# ProProject__2_2023-12-08.net
KiCad netlist of a schematic drawn in EasyEDA Pro
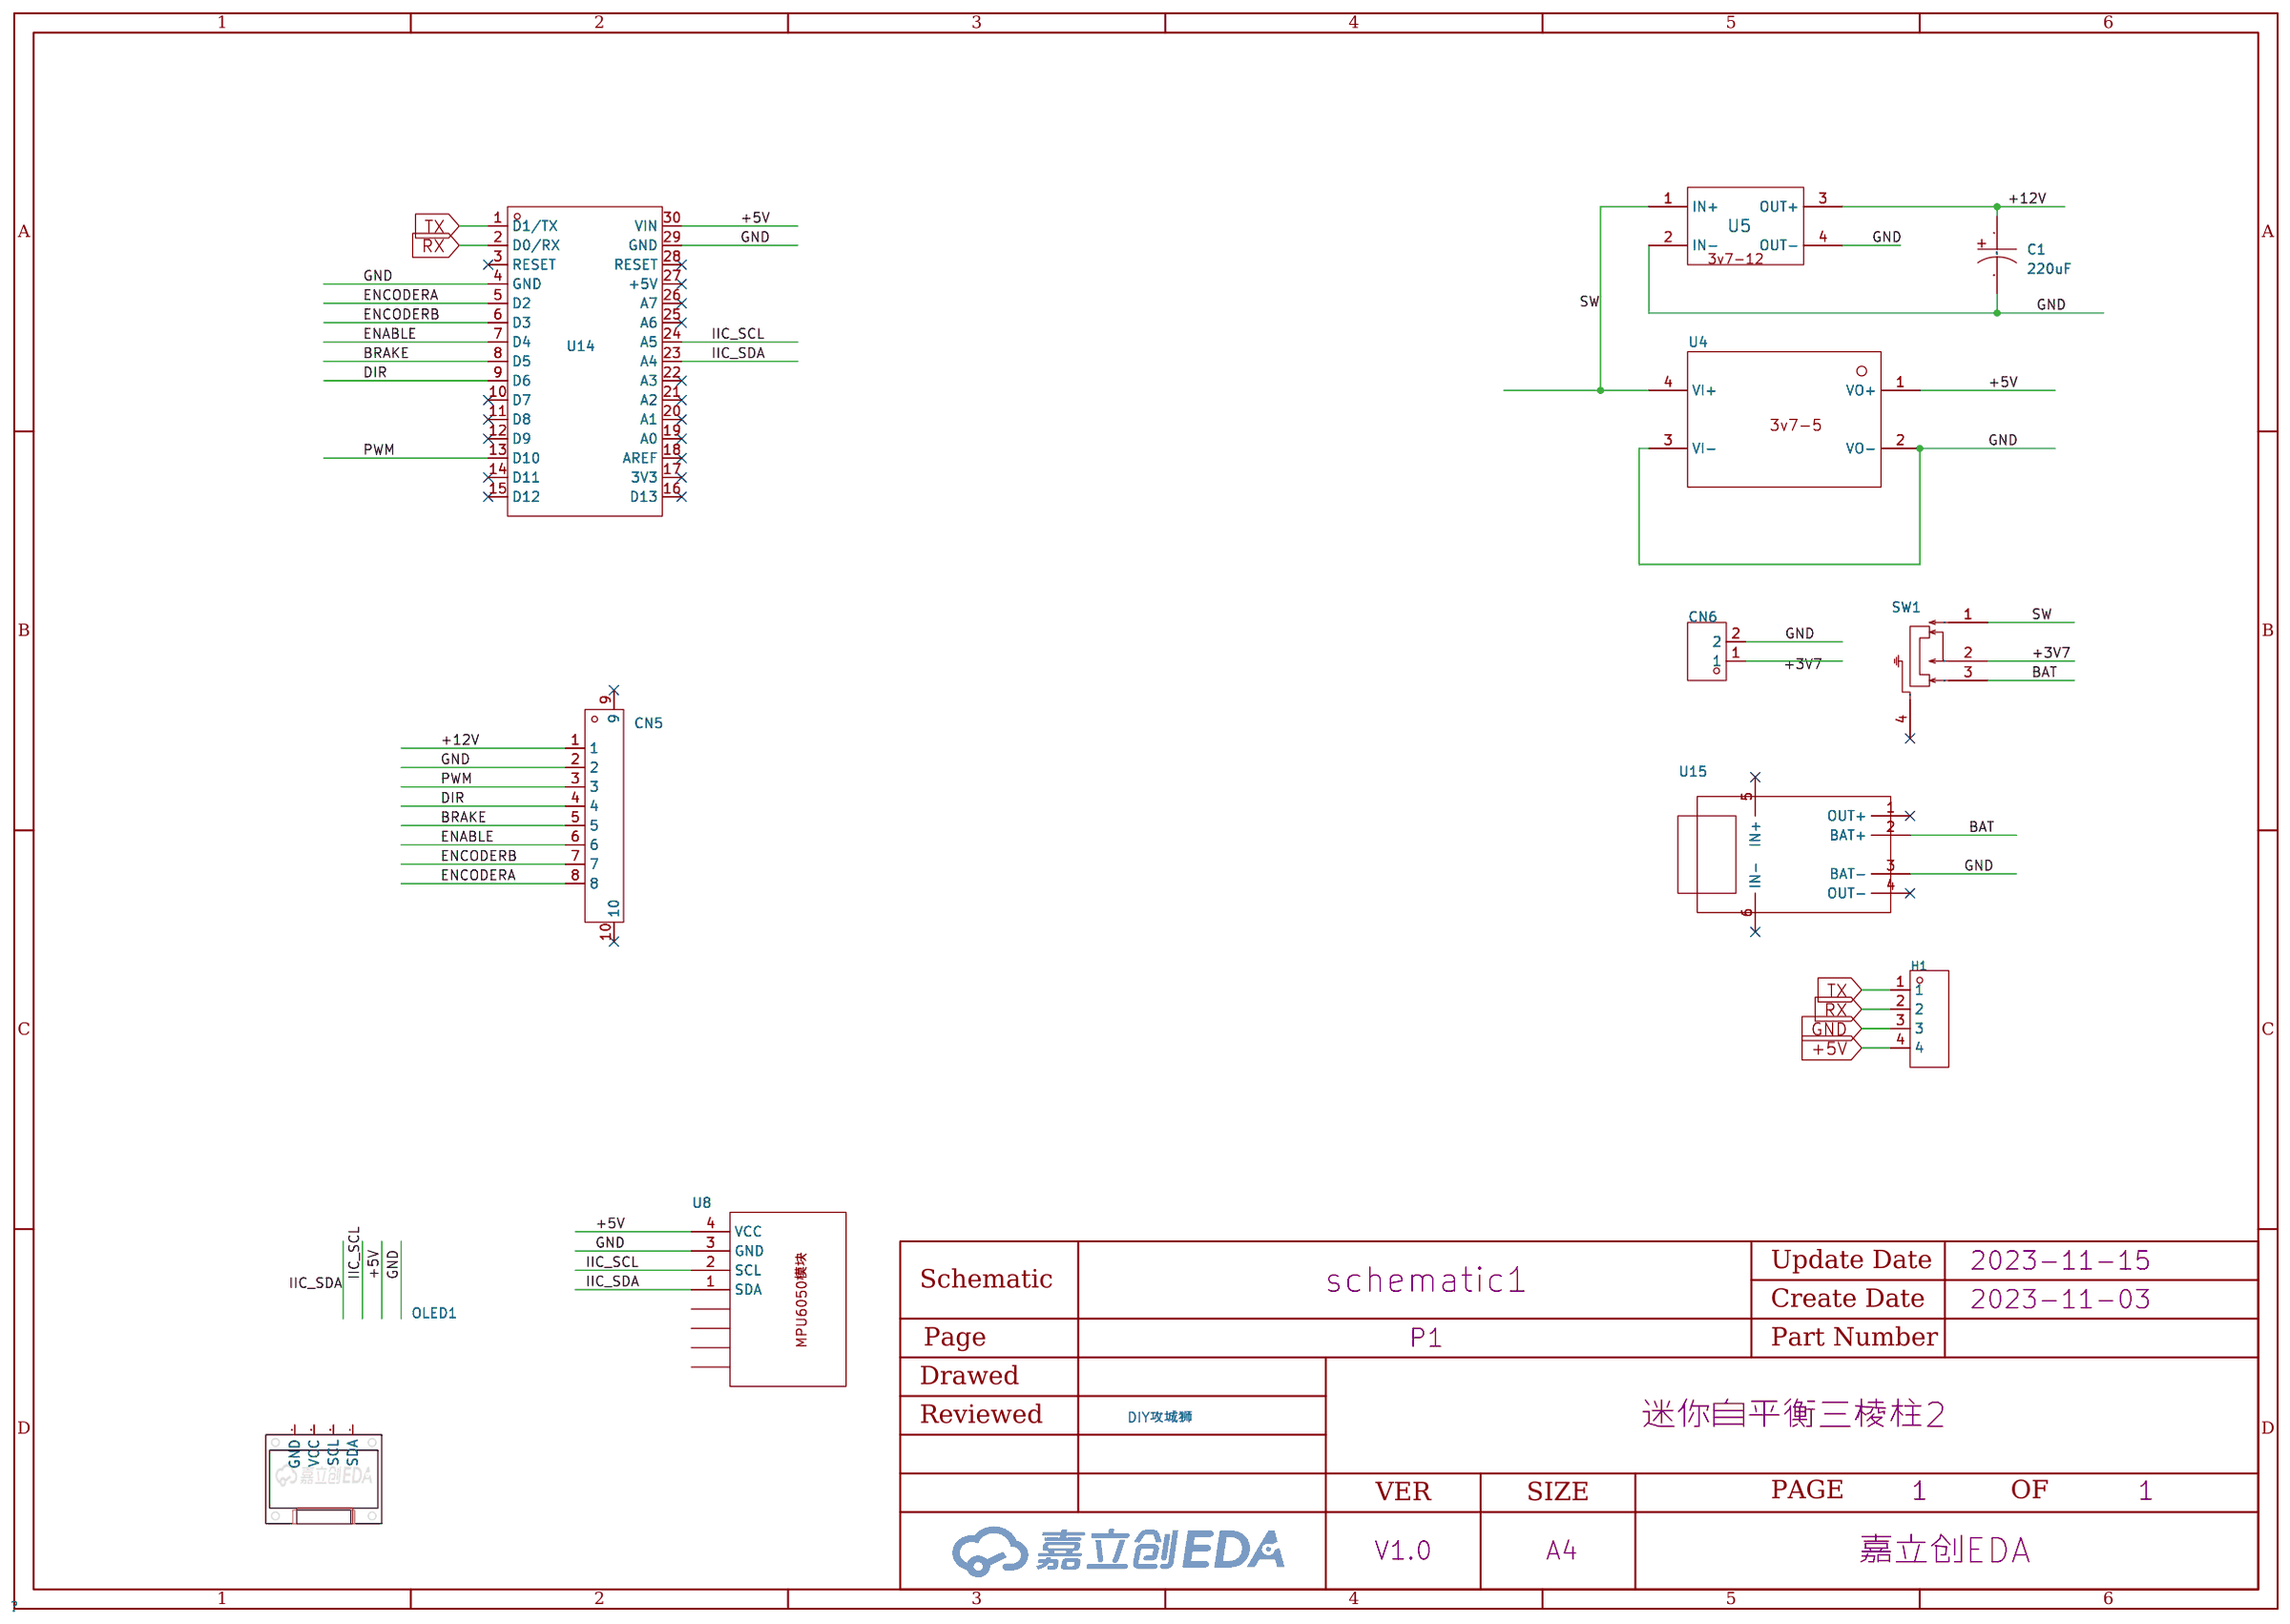
[diagram p0: schematic sheet]

(export (version "E")
  (design (tool "Eeschema 10.0.6"))
  (components
    (comp (ref "C1")
      (value "220uF")
      (footprint "easyedapro:CAP-SMD_BD8.0-L8.3-W8.3-FD")
      (fields (field (name "Manufacturer Part") "EEEFP1V221AP") (field (name "Manufacturer") "PANASONIC(松下)"))
      (libsource (lib "easyedapro") (part "EEEFP1V221AP"))
    )
    (comp (ref "CN5")
      (value "GH1.25-8PLTPZ")
      (footprint "easyedapro:CONN-SMD_GH1.25-8PLTPZ")
      (fields (field (name "Manufacturer") "BOOMELE(博穆精密)"))
      (libsource (lib "easyedapro") (part "GH1.25-8PLTPZ"))
    )
    (comp (ref "CN6")
      (value "B2B-XH-A(LF)(SN)")
      (footprint "easyedapro:CONN-TH_2P-P2.50-XH2.54-2P")
      (fields (field (name "Manufacturer") "JST"))
      (libsource (lib "easyedapro") (part "HX25037-2A_C9900012767"))
    )
    (comp (ref "H1")
      (value "~")
      (footprint "easyedapro:HDR-TH_4P-P2.54-V-M")
      (libsource (lib "easyedapro") (part "PZ254V-11-04P"))
    )
    (comp (ref "OLED1")
      (value "~")
      (footprint "easyedapro:0.96OLED_4P")
      (libsource (lib "easyedapro") (part "0.96OLED模块_4P"))
    )
    (comp (ref "SW1")
      (value "HX MSK12CO2-BBTM")
      (footprint "easyedapro:SW-SMD_MSK12C02-HB")
      (fields (field (name "Manufacturer") "hanxia(韩下)"))
      (libsource (lib "easyedapro") (part "HX MSK12CO2-BBTM"))
    )
    (comp (ref "U4")
      (value "DM13-05")
      (footprint "easyedapro:DM13-05")
      (libsource (lib "easyedapro") (part "DM13-05"))
    )
    (comp (ref "U5")
      (value "~")
      (footprint "easyedapro:DC3V7-DC12")
      (libsource (lib "easyedapro") (part "DC3V7-DC12"))
    )
    (comp (ref "U8")
      (value "~")
      (footprint "easyedapro:MPU-6050模块")
      (description "MPU-6050模块")
      (libsource (lib "easyedapro") (part "MPU-6050模块"))
    )
    (comp (ref "U14")
      (value "ARDUINO_NANO")
      (footprint "easyedapro:COMM-TH_ARDUINO_NANO")
      (libsource (lib "easyedapro") (part "ARDUINO_NANO"))
    )
    (comp (ref "U15")
      (value "~")
      (footprint "easyedapro:TP4057模块封装")
      (libsource (lib "easyedapro") (part "TP4057模块"))
    )
  )
  (nets
    (net (code "1") (name "+5V") (class "Default")
      (node (ref "H1") (pin "4") (pinfunction "4_4") (pintype "input"))
      (node (ref "U14") (pin "30") (pinfunction "VIN_30") (pintype "input"))
      (node (ref "U4") (pin "1") (pinfunction "VO+_1") (pintype "unspecified"))
      (node (ref "U8") (pin "4") (pinfunction "VCC_4") (pintype "input"))
    )
    (net (code "2") (name "/+3V7") (class "Default")
      (node (ref "CN6") (pin "1") (pinfunction "1_1") (pintype "input"))
      (node (ref "SW1") (pin "2") (pinfunction "2_2") (pintype "input"))
    )
    (net (code "3") (name "/+12V") (class "Default")
      (node (ref "C1") (pin "1") (pinfunction "1_1") (pintype "input"))
      (node (ref "CN5") (pin "1") (pinfunction "1_1") (pintype "input"))
      (node (ref "U5") (pin "3") (pinfunction "OUT+_3") (pintype "unspecified"))
    )
    (net (code "4") (name "/BAT") (class "Default")
      (node (ref "SW1") (pin "3") (pinfunction "3_3") (pintype "input"))
      (node (ref "U15") (pin "2") (pinfunction "BAT+_2") (pintype "input"))
    )
    (net (code "5") (name "/BRAKE") (class "Default")
      (node (ref "CN5") (pin "5") (pinfunction "5_5") (pintype "input"))
      (node (ref "U14") (pin "8") (pinfunction "D5_8") (pintype "input"))
    )
    (net (code "6") (name "/DIR") (class "Default")
      (node (ref "CN5") (pin "4") (pinfunction "4_4") (pintype "input"))
      (node (ref "U14") (pin "9") (pinfunction "D6_9") (pintype "input"))
    )
    (net (code "7") (name "/ENABLE") (class "Default")
      (node (ref "CN5") (pin "6") (pinfunction "6_6") (pintype "input"))
      (node (ref "U14") (pin "7") (pinfunction "D4_7") (pintype "input"))
    )
    (net (code "8") (name "/ENCODERA") (class "Default")
      (node (ref "CN5") (pin "8") (pinfunction "8_8") (pintype "input"))
      (node (ref "U14") (pin "5") (pinfunction "D2_5") (pintype "input"))
    )
    (net (code "9") (name "/ENCODERB") (class "Default")
      (node (ref "CN5") (pin "7") (pinfunction "7_7") (pintype "input"))
      (node (ref "U14") (pin "6") (pinfunction "D3_6") (pintype "input"))
    )
    (net (code "10") (name "/IIC_SCL") (class "Default")
      (node (ref "U14") (pin "24") (pinfunction "A5_24") (pintype "input"))
      (node (ref "U8") (pin "2") (pinfunction "SCL_2") (pintype "input"))
    )
    (net (code "11") (name "/IIC_SDA") (class "Default")
      (node (ref "U14") (pin "23") (pinfunction "A4_23") (pintype "input"))
      (node (ref "U8") (pin "1") (pinfunction "SDA_1") (pintype "input"))
    )
    (net (code "12") (name "/PWM") (class "Default")
      (node (ref "CN5") (pin "3") (pinfunction "3_3") (pintype "input"))
      (node (ref "U14") (pin "13") (pinfunction "D10_13") (pintype "input"))
    )
    (net (code "13") (name "/SW") (class "Default")
      (node (ref "SW1") (pin "1") (pinfunction "1_1") (pintype "input"))
      (node (ref "U4") (pin "4") (pinfunction "VI+_4") (pintype "unspecified"))
      (node (ref "U5") (pin "1") (pinfunction "IN+_1") (pintype "unspecified"))
    )
    (net (code "14") (name "GND") (class "Default")
      (node (ref "C1") (pin "2") (pinfunction "2_2") (pintype "input"))
      (node (ref "CN5") (pin "2") (pinfunction "2_2") (pintype "input"))
      (node (ref "CN6") (pin "2") (pinfunction "2_2") (pintype "input"))
      (node (ref "H1") (pin "3") (pinfunction "3_3") (pintype "input"))
      (node (ref "U14") (pin "29") (pinfunction "GND_29") (pintype "input"))
      (node (ref "U14") (pin "4") (pinfunction "GND_4") (pintype "input"))
      (node (ref "U15") (pin "3") (pinfunction "BAT-_3") (pintype "input"))
      (node (ref "U4") (pin "2") (pinfunction "VO-_2") (pintype "unspecified"))
      (node (ref "U4") (pin "3") (pinfunction "VI-_3") (pintype "unspecified"))
      (node (ref "U5") (pin "2") (pinfunction "IN-_2") (pintype "unspecified"))
      (node (ref "U5") (pin "4") (pinfunction "OUT-_4") (pintype "unspecified"))
      (node (ref "U8") (pin "3") (pinfunction "GND_3") (pintype "input"))
    )
    (net (code "15") (name "RX") (class "Default")
      (node (ref "H1") (pin "2") (pinfunction "2_2") (pintype "input"))
      (node (ref "U14") (pin "2") (pinfunction "D0/RX_2") (pintype "input"))
    )
    (net (code "16") (name "TX") (class "Default")
      (node (ref "H1") (pin "1") (pinfunction "1_1") (pintype "input"))
      (node (ref "U14") (pin "1") (pinfunction "D1/TX_1") (pintype "input"))
    )
    (net (code "17") (name "unconnected-(CN5-Pad9)") (class "Default")
      (node (ref "CN5") (pin "9") (pinfunction "9_9") (pintype "input+no_connect"))
    )
    (net (code "18") (name "unconnected-(CN5-Pad10)") (class "Default")
      (node (ref "CN5") (pin "10") (pinfunction "10_10") (pintype "input+no_connect"))
    )
    (net (code "19") (name "unconnected-(OLED1-GND-Pad1)") (class "Default")
      (node (ref "OLED1") (pin "1") (pinfunction "GND_1") (pintype "input"))
    )
    (net (code "20") (name "unconnected-(OLED1-SCL-Pad3)") (class "Default")
      (node (ref "OLED1") (pin "3") (pinfunction "SCL_3") (pintype "input"))
    )
    (net (code "21") (name "unconnected-(OLED1-SDA-Pad4)") (class "Default")
      (node (ref "OLED1") (pin "4") (pinfunction "SDA_4") (pintype "input"))
    )
    (net (code "22") (name "unconnected-(OLED1-VCC-Pad2)") (class "Default")
      (node (ref "OLED1") (pin "2") (pinfunction "VCC_2") (pintype "input"))
    )
    (net (code "23") (name "unconnected-(SW1-Pad4)") (class "Default")
      (node (ref "SW1") (pin "4") (pinfunction "4_4") (pintype "input+no_connect"))
    )
    (net (code "24") (name "unconnected-(U14-+5V-Pad27)") (class "Default")
      (node (ref "U14") (pin "27") (pinfunction "+5V_27") (pintype "input+no_connect"))
    )
    (net (code "25") (name "unconnected-(U14-3V3-Pad17)") (class "Default")
      (node (ref "U14") (pin "17") (pinfunction "3V3_17") (pintype "input+no_connect"))
    )
    (net (code "26") (name "unconnected-(U14-A0-Pad19)") (class "Default")
      (node (ref "U14") (pin "19") (pinfunction "A0_19") (pintype "input+no_connect"))
    )
    (net (code "27") (name "unconnected-(U14-A1-Pad20)") (class "Default")
      (node (ref "U14") (pin "20") (pinfunction "A1_20") (pintype "input+no_connect"))
    )
    (net (code "28") (name "unconnected-(U14-A2-Pad21)") (class "Default")
      (node (ref "U14") (pin "21") (pinfunction "A2_21") (pintype "input+no_connect"))
    )
    (net (code "29") (name "unconnected-(U14-A3-Pad22)") (class "Default")
      (node (ref "U14") (pin "22") (pinfunction "A3_22") (pintype "input+no_connect"))
    )
    (net (code "30") (name "unconnected-(U14-A6-Pad25)") (class "Default")
      (node (ref "U14") (pin "25") (pinfunction "A6_25") (pintype "input+no_connect"))
    )
    (net (code "31") (name "unconnected-(U14-A7-Pad26)") (class "Default")
      (node (ref "U14") (pin "26") (pinfunction "A7_26") (pintype "input+no_connect"))
    )
    (net (code "32") (name "unconnected-(U14-AREF-Pad18)") (class "Default")
      (node (ref "U14") (pin "18") (pinfunction "AREF_18") (pintype "input+no_connect"))
    )
    (net (code "33") (name "unconnected-(U14-D7-Pad10)") (class "Default")
      (node (ref "U14") (pin "10") (pinfunction "D7_10") (pintype "input+no_connect"))
    )
    (net (code "34") (name "unconnected-(U14-D8-Pad11)") (class "Default")
      (node (ref "U14") (pin "11") (pinfunction "D8_11") (pintype "input+no_connect"))
    )
    (net (code "35") (name "unconnected-(U14-D9-Pad12)") (class "Default")
      (node (ref "U14") (pin "12") (pinfunction "D9_12") (pintype "input+no_connect"))
    )
    (net (code "36") (name "unconnected-(U14-D11-Pad14)") (class "Default")
      (node (ref "U14") (pin "14") (pinfunction "D11_14") (pintype "input+no_connect"))
    )
    (net (code "37") (name "unconnected-(U14-D12-Pad15)") (class "Default")
      (node (ref "U14") (pin "15") (pinfunction "D12_15") (pintype "input+no_connect"))
    )
    (net (code "38") (name "unconnected-(U14-D13-Pad16)") (class "Default")
      (node (ref "U14") (pin "16") (pinfunction "D13_16") (pintype "input+no_connect"))
    )
    (net (code "39") (name "unconnected-(U14-RESET-Pad3)") (class "Default")
      (node (ref "U14") (pin "3") (pinfunction "RESET_3") (pintype "input+no_connect"))
    )
    (net (code "40") (name "unconnected-(U14-RESET-Pad28)") (class "Default")
      (node (ref "U14") (pin "28") (pinfunction "RESET_28") (pintype "input+no_connect"))
    )
    (net (code "41") (name "unconnected-(U15-IN+-Pad5)") (class "Default")
      (node (ref "U15") (pin "5") (pinfunction "IN+_5") (pintype "input+no_connect"))
    )
    (net (code "42") (name "unconnected-(U15-IN--Pad6)") (class "Default")
      (node (ref "U15") (pin "6") (pinfunction "IN-_6") (pintype "input+no_connect"))
    )
    (net (code "43") (name "unconnected-(U15-OUT+-Pad1)") (class "Default")
      (node (ref "U15") (pin "1") (pinfunction "OUT+_1") (pintype "input+no_connect"))
    )
    (net (code "44") (name "unconnected-(U15-OUT--Pad4)") (class "Default")
      (node (ref "U15") (pin "4") (pinfunction "OUT-_4") (pintype "input+no_connect"))
    )
  )
)
